# pilight_sys.net
KiCad netlist of a schematic drawn in EAGLE
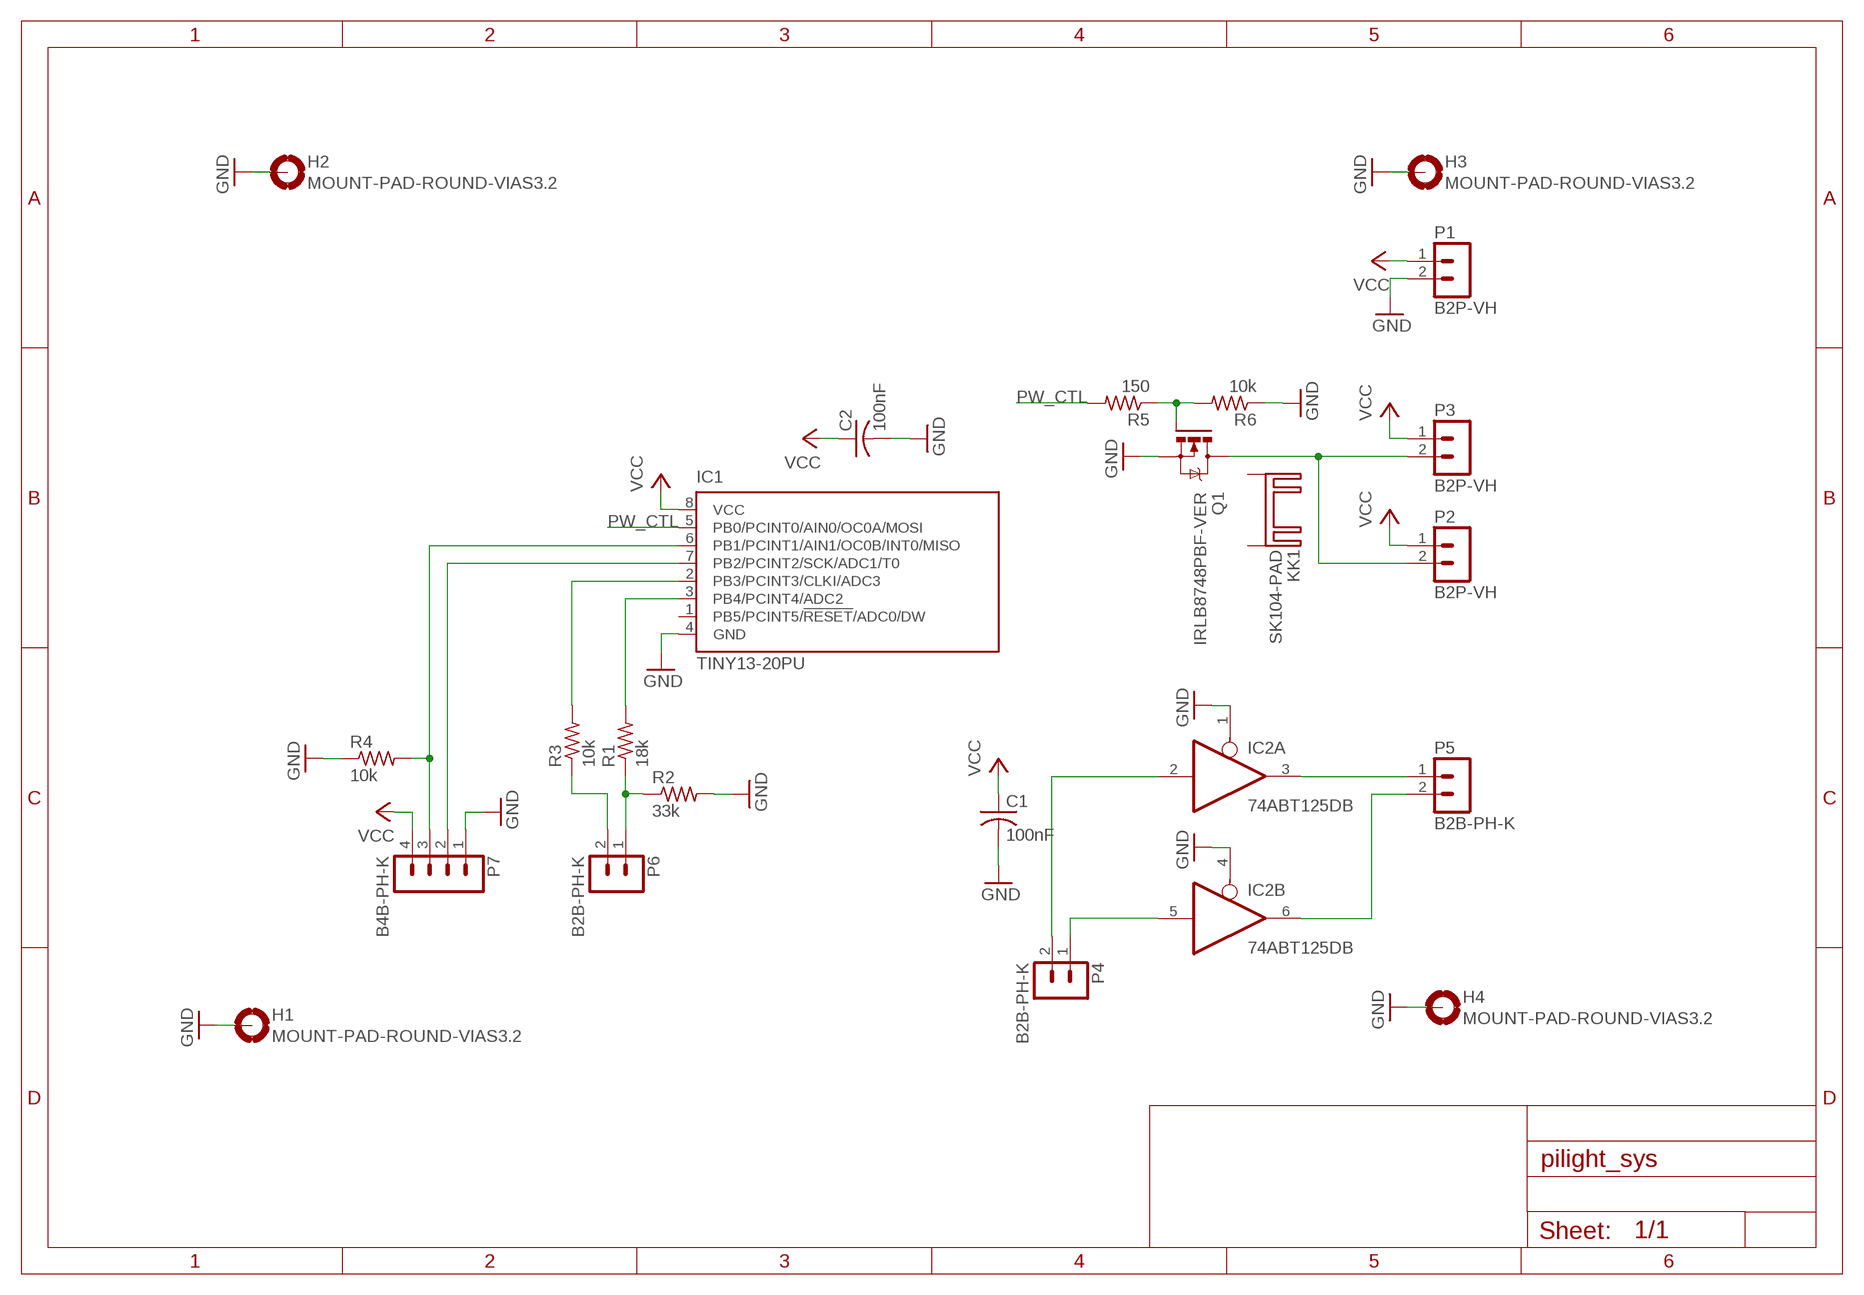
[diagram p0: schematic, sheet 1]

(export (version "E")
  (design (tool "Eeschema 10.0.6"))
  (components
    (comp (ref "C1")
      (value "100nF")
      (footprint "eagle-import:C0805")
      (libsource (lib "eagle-import") (part "C-USC0805"))
    )
    (comp (ref "C2")
      (value "100nF")
      (footprint "eagle-import:C0805")
      (libsource (lib "eagle-import") (part "C-USC0805"))
    )
    (comp (ref "H1")
      (value "MOUNT-PAD-ROUND-VIAS3.2")
      (footprint "eagle-import:3,2-PAD")
      (libsource (lib "eagle-import") (part "MOUNT-PAD-ROUND-VIAS3.2"))
    )
    (comp (ref "H2")
      (value "MOUNT-PAD-ROUND-VIAS3.2")
      (footprint "eagle-import:3,2-PAD")
      (libsource (lib "eagle-import") (part "MOUNT-PAD-ROUND-VIAS3.2"))
    )
    (comp (ref "H3")
      (value "MOUNT-PAD-ROUND-VIAS3.2")
      (footprint "eagle-import:3,2-PAD")
      (libsource (lib "eagle-import") (part "MOUNT-PAD-ROUND-VIAS3.2"))
    )
    (comp (ref "H4")
      (value "MOUNT-PAD-ROUND-VIAS3.2")
      (footprint "eagle-import:3,2-PAD")
      (libsource (lib "eagle-import") (part "MOUNT-PAD-ROUND-VIAS3.2"))
    )
    (comp (ref "IC1")
      (value "TINY13-20PU")
      (footprint "eagle-import:DIL08")
      (fields (field (name "MPN") "ATTINY13-20PU"))
      (libsource (lib "eagle-import") (part "TINY13PU-20"))
    )
    (comp (ref "IC2")
      (value "74ABT125DB")
      (footprint "eagle-import:SSOP14")
      (libsource (lib "eagle-import") (part "74125DBABT"))
    )
    (comp (ref "KK1")
      (value "SK104-PAD")
      (footprint "eagle-import:SK104-PAD")
      (libsource (lib "eagle-import") (part "SK104-PAD"))
    )
    (comp (ref "P1")
      (value "B2P-VH")
      (footprint "eagle-import:B2P-VH")
      (libsource (lib "eagle-import") (part "B2P-VH"))
    )
    (comp (ref "P2")
      (value "B2P-VH")
      (footprint "eagle-import:B2P-VH")
      (libsource (lib "eagle-import") (part "B2P-VH"))
    )
    (comp (ref "P3")
      (value "B2P-VH")
      (footprint "eagle-import:B2P-VH")
      (libsource (lib "eagle-import") (part "B2P-VH"))
    )
    (comp (ref "P4")
      (value "B2B-PH-K")
      (footprint "eagle-import:B2B-PH-K")
      (libsource (lib "eagle-import") (part "B2B-PH-K"))
    )
    (comp (ref "P5")
      (value "B2B-PH-K")
      (footprint "eagle-import:B2B-PH-K")
      (libsource (lib "eagle-import") (part "B2B-PH-K"))
    )
    (comp (ref "P6")
      (value "B2B-PH-K")
      (footprint "eagle-import:B2B-PH-K")
      (libsource (lib "eagle-import") (part "B2B-PH-K"))
    )
    (comp (ref "P7")
      (value "B4B-PH-K")
      (footprint "eagle-import:B4B-PH-K")
      (libsource (lib "eagle-import") (part "B4B-PH-K"))
    )
    (comp (ref "Q1")
      (value "IRLB8748PBF-VER")
      (footprint "eagle-import:TO220AV")
      (libsource (lib "eagle-import") (part "IRLB8748PBF-VER"))
    )
    (comp (ref "R1")
      (value "18k")
      (footprint "eagle-import:R0805")
      (libsource (lib "eagle-import") (part "R-US_R0805"))
    )
    (comp (ref "R2")
      (value "33k")
      (footprint "eagle-import:R0805")
      (libsource (lib "eagle-import") (part "R-US_R0805"))
    )
    (comp (ref "R3")
      (value "10k")
      (footprint "eagle-import:R0805")
      (libsource (lib "eagle-import") (part "R-US_R0805"))
    )
    (comp (ref "R4")
      (value "10k")
      (footprint "eagle-import:R0805")
      (libsource (lib "eagle-import") (part "R-US_R0805"))
    )
    (comp (ref "R5")
      (value "150")
      (footprint "eagle-import:R0805")
      (libsource (lib "eagle-import") (part "R-US_R0805"))
    )
    (comp (ref "R6")
      (value "10k")
      (footprint "eagle-import:R0805")
      (libsource (lib "eagle-import") (part "R-US_R0805"))
    )
  )
  (nets
    (net (code "1") (name "/PW_CTL") (class "Default")
      (node (ref "IC1") (pin "5") (pinfunction "PB0/PCINT0/AIN0/OC0A/MOSI_5") (pintype "bidirectional"))
      (node (ref "R5") (pin "2") (pinfunction "2_2") (pintype "passive"))
    )
    (net (code "2") (name "GND") (class "Default")
      (node (ref "C1") (pin "2") (pinfunction "2_2") (pintype "passive"))
      (node (ref "C2") (pin "2") (pinfunction "2_2") (pintype "passive"))
      (node (ref "H1") (pin "B3,2") (pinfunction "MOUNT_B3,2") (pintype "passive"))
      (node (ref "H1") (pin "P$1") (pinfunction "MOUNT_P$1") (pintype "passive"))
      (node (ref "H1") (pin "P$2") (pinfunction "MOUNT_P$2") (pintype "passive"))
      (node (ref "H1") (pin "P$3") (pinfunction "MOUNT_P$3") (pintype "passive"))
      (node (ref "H1") (pin "P$4") (pinfunction "MOUNT_P$4") (pintype "passive"))
      (node (ref "H1") (pin "P$5") (pinfunction "MOUNT_P$5") (pintype "passive"))
      (node (ref "H1") (pin "P$6") (pinfunction "MOUNT_P$6") (pintype "passive"))
      (node (ref "H1") (pin "P$7") (pinfunction "MOUNT_P$7") (pintype "passive"))
      (node (ref "H1") (pin "P$8") (pinfunction "MOUNT_P$8") (pintype "passive"))
      (node (ref "H1") (pin "P$9") (pinfunction "MOUNT_P$9") (pintype "passive"))
      (node (ref "H2") (pin "B3,2") (pinfunction "MOUNT_B3,2") (pintype "passive"))
      (node (ref "H2") (pin "P$1") (pinfunction "MOUNT_P$1") (pintype "passive"))
      (node (ref "H2") (pin "P$2") (pinfunction "MOUNT_P$2") (pintype "passive"))
      (node (ref "H2") (pin "P$3") (pinfunction "MOUNT_P$3") (pintype "passive"))
      (node (ref "H2") (pin "P$4") (pinfunction "MOUNT_P$4") (pintype "passive"))
      (node (ref "H2") (pin "P$5") (pinfunction "MOUNT_P$5") (pintype "passive"))
      (node (ref "H2") (pin "P$6") (pinfunction "MOUNT_P$6") (pintype "passive"))
      (node (ref "H2") (pin "P$7") (pinfunction "MOUNT_P$7") (pintype "passive"))
      (node (ref "H2") (pin "P$8") (pinfunction "MOUNT_P$8") (pintype "passive"))
      (node (ref "H2") (pin "P$9") (pinfunction "MOUNT_P$9") (pintype "passive"))
      (node (ref "H3") (pin "B3,2") (pinfunction "MOUNT_B3,2") (pintype "passive"))
      (node (ref "H3") (pin "P$1") (pinfunction "MOUNT_P$1") (pintype "passive"))
      (node (ref "H3") (pin "P$2") (pinfunction "MOUNT_P$2") (pintype "passive"))
      (node (ref "H3") (pin "P$3") (pinfunction "MOUNT_P$3") (pintype "passive"))
      (node (ref "H3") (pin "P$4") (pinfunction "MOUNT_P$4") (pintype "passive"))
      (node (ref "H3") (pin "P$5") (pinfunction "MOUNT_P$5") (pintype "passive"))
      (node (ref "H3") (pin "P$6") (pinfunction "MOUNT_P$6") (pintype "passive"))
      (node (ref "H3") (pin "P$7") (pinfunction "MOUNT_P$7") (pintype "passive"))
      (node (ref "H3") (pin "P$8") (pinfunction "MOUNT_P$8") (pintype "passive"))
      (node (ref "H3") (pin "P$9") (pinfunction "MOUNT_P$9") (pintype "passive"))
      (node (ref "H4") (pin "B3,2") (pinfunction "MOUNT_B3,2") (pintype "passive"))
      (node (ref "H4") (pin "P$1") (pinfunction "MOUNT_P$1") (pintype "passive"))
      (node (ref "H4") (pin "P$2") (pinfunction "MOUNT_P$2") (pintype "passive"))
      (node (ref "H4") (pin "P$3") (pinfunction "MOUNT_P$3") (pintype "passive"))
      (node (ref "H4") (pin "P$4") (pinfunction "MOUNT_P$4") (pintype "passive"))
      (node (ref "H4") (pin "P$5") (pinfunction "MOUNT_P$5") (pintype "passive"))
      (node (ref "H4") (pin "P$6") (pinfunction "MOUNT_P$6") (pintype "passive"))
      (node (ref "H4") (pin "P$7") (pinfunction "MOUNT_P$7") (pintype "passive"))
      (node (ref "H4") (pin "P$8") (pinfunction "MOUNT_P$8") (pintype "passive"))
      (node (ref "H4") (pin "P$9") (pinfunction "MOUNT_P$9") (pintype "passive"))
      (node (ref "IC1") (pin "4") (pinfunction "GND_4") (pintype "power_in"))
      (node (ref "IC2") (pin "1") (pinfunction "OE_1") (pintype "input"))
      (node (ref "IC2") (pin "4") (pinfunction "OE_4") (pintype "input"))
      (node (ref "P1") (pin "2") (pinfunction "2_2") (pintype "passive"))
      (node (ref "P7") (pin "1") (pinfunction "1_1") (pintype "passive"))
      (node (ref "Q1") (pin "S") (pinfunction "S_S") (pintype "passive"))
      (node (ref "R2") (pin "2") (pinfunction "2_2") (pintype "passive"))
      (node (ref "R4") (pin "1") (pinfunction "1_1") (pintype "passive"))
      (node (ref "R6") (pin "1") (pinfunction "1_1") (pintype "passive"))
    )
    (net (code "3") (name "Net-(IC1-PB1{slash}PCINT1{slash}AIN1{slash}OC0B{slash}INT0{slash}MISO)") (class "Default")
      (node (ref "IC1") (pin "6") (pinfunction "PB1/PCINT1/AIN1/OC0B/INT0/MISO_6") (pintype "bidirectional"))
      (node (ref "P7") (pin "3") (pinfunction "3_3") (pintype "passive"))
      (node (ref "R4") (pin "2") (pinfunction "2_2") (pintype "passive"))
    )
    (net (code "4") (name "Net-(IC1-PB2{slash}PCINT2{slash}SCK{slash}ADC1{slash}T0)") (class "Default")
      (node (ref "IC1") (pin "7") (pinfunction "PB2/PCINT2/SCK/ADC1/T0_7") (pintype "bidirectional"))
      (node (ref "P7") (pin "2") (pinfunction "2_2") (pintype "passive"))
    )
    (net (code "5") (name "Net-(IC1-PB3{slash}PCINT3{slash}CLKI{slash}ADC3)") (class "Default")
      (node (ref "IC1") (pin "2") (pinfunction "PB3/PCINT3/CLKI/ADC3_2") (pintype "bidirectional"))
      (node (ref "R3") (pin "2") (pinfunction "2_2") (pintype "passive"))
    )
    (net (code "6") (name "Net-(IC1-PB4{slash}PCINT4{slash}ADC2)") (class "Default")
      (node (ref "IC1") (pin "3") (pinfunction "PB4/PCINT4/ADC2_3") (pintype "bidirectional"))
      (node (ref "R1") (pin "2") (pinfunction "2_2") (pintype "passive"))
    )
    (net (code "7") (name "Net-(IC2A-I)") (class "Default")
      (node (ref "IC2") (pin "2") (pinfunction "I_2") (pintype "input"))
      (node (ref "P4") (pin "2") (pinfunction "2_2") (pintype "passive"))
    )
    (net (code "8") (name "Net-(IC2A-O)") (class "Default")
      (node (ref "IC2") (pin "3") (pinfunction "O_3") (pintype "tri_state"))
      (node (ref "P5") (pin "1") (pinfunction "1_1") (pintype "passive"))
    )
    (net (code "9") (name "Net-(IC2B-I)") (class "Default")
      (node (ref "IC2") (pin "5") (pinfunction "I_5") (pintype "input"))
      (node (ref "P4") (pin "1") (pinfunction "1_1") (pintype "passive"))
    )
    (net (code "10") (name "Net-(IC2B-O)") (class "Default")
      (node (ref "IC2") (pin "6") (pinfunction "O_6") (pintype "tri_state"))
      (node (ref "P5") (pin "2") (pinfunction "2_2") (pintype "passive"))
    )
    (net (code "11") (name "Net-(P2-Pad2)") (class "Default")
      (node (ref "P2") (pin "2") (pinfunction "2_2") (pintype "passive"))
      (node (ref "P3") (pin "2") (pinfunction "2_2") (pintype "passive"))
      (node (ref "Q1") (pin "D") (pinfunction "D_D") (pintype "passive"))
    )
    (net (code "12") (name "Net-(P6-Pad1)") (class "Default")
      (node (ref "P6") (pin "1") (pinfunction "1_1") (pintype "passive"))
      (node (ref "R1") (pin "1") (pinfunction "1_1") (pintype "passive"))
      (node (ref "R2") (pin "1") (pinfunction "1_1") (pintype "passive"))
    )
    (net (code "13") (name "Net-(P6-Pad2)") (class "Default")
      (node (ref "P6") (pin "2") (pinfunction "2_2") (pintype "passive"))
      (node (ref "R3") (pin "1") (pinfunction "1_1") (pintype "passive"))
    )
    (net (code "14") (name "Net-(Q1-PadG)") (class "Default")
      (node (ref "Q1") (pin "G") (pinfunction "G_G") (pintype "passive"))
      (node (ref "R5") (pin "1") (pinfunction "1_1") (pintype "passive"))
      (node (ref "R6") (pin "2") (pinfunction "2_2") (pintype "passive"))
    )
    (net (code "15") (name "VCC") (class "Default")
      (node (ref "C1") (pin "1") (pinfunction "1_1") (pintype "passive"))
      (node (ref "C2") (pin "1") (pinfunction "1_1") (pintype "passive"))
      (node (ref "IC1") (pin "8") (pinfunction "VCC_8") (pintype "power_in"))
      (node (ref "P1") (pin "1") (pinfunction "1_1") (pintype "passive"))
      (node (ref "P2") (pin "1") (pinfunction "1_1") (pintype "passive"))
      (node (ref "P3") (pin "1") (pinfunction "1_1") (pintype "passive"))
      (node (ref "P7") (pin "4") (pinfunction "4_4") (pintype "passive"))
    )
    (net (code "16") (name "unconnected-(IC1-PB5{slash}PCINT5{slash}~{RESET}{slash}ADC0{slash}DW-Pad1)") (class "Default")
      (node (ref "IC1") (pin "1") (pinfunction "PB5/PCINT5/~{RESET}/ADC0/DW_1") (pintype "bidirectional"))
    )
    (net (code "17") (name "unconnected-(KK1-K-PadK1)") (class "Default")
      (node (ref "KK1") (pin "K1") (pinfunction "K_K1") (pintype "passive"))
    )
    (net (code "18") (name "unconnected-(KK1-K-PadK2)") (class "Default")
      (node (ref "KK1") (pin "K2") (pinfunction "K_K2") (pintype "passive"))
    )
  )
)
